# FINAL_MA.net
KiCad netlist of a schematic drawn in EAGLE
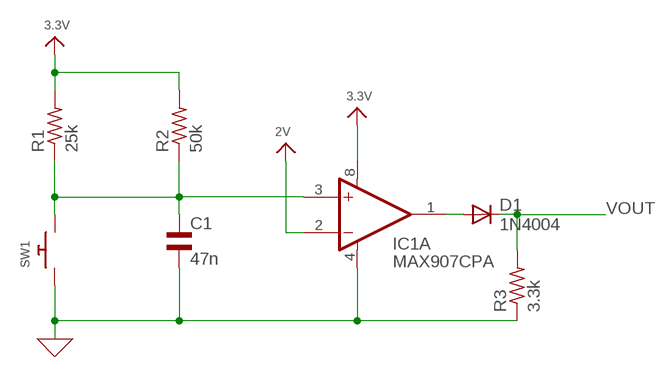
[diagram p0: schematic, sheet 1]

(export (version "E")
  (design (tool "Eeschema 10.0.6"))
  (components
    (comp (ref "C1")
      (value "47n")
      (footprint "eagle-import:EU25-10")
      (libsource (lib "eagle-import") (part "EL-BI25-10AXIAL"))
    )
    (comp (ref "D1")
      (value "1N4004")
      (footprint "eagle-import:DO41-10")
      (libsource (lib "eagle-import") (part "1N4004"))
    )
    (comp (ref "IC1")
      (value "MAX907CPA")
      (footprint "eagle-import:DIL08")
      (fields (field (name "MF") "MAXIM"))
      (libsource (lib "eagle-import") (part "MAX907CPA"))
    )
    (comp (ref "R1")
      (value "25k")
      (footprint "eagle-import:0204_5")
      (libsource (lib "eagle-import") (part "R-US_0204/5"))
    )
    (comp (ref "R2")
      (value "50k")
      (footprint "eagle-import:0204_5")
      (libsource (lib "eagle-import") (part "R-US_0204/5"))
    )
    (comp (ref "R3")
      (value "3.3k")
      (footprint "eagle-import:0204_5")
      (libsource (lib "eagle-import") (part "R-US_0204/5"))
    )
    (comp (ref "SW1")
      (value "SWITCH_PUSHBUTTONEVQ-PE")
      (footprint "eagle-import:TACT_PANA-EVQ")
      (libsource (lib "eagle-import") (part "SWITCH_PUSHBUTTONEVQ-PE"))
    )
  )
  (nets
    (net (code "1") (name "/VOUT") (class "Default")
      (node (ref "D1") (pin "C") (pinfunction "C_C") (pintype "passive"))
      (node (ref "R3") (pin "2") (pinfunction "2_2") (pintype "passive"))
    )
    (net (code "2") (name "2V") (class "Default")
      (node (ref "IC1") (pin "2") (pinfunction "-IN_2") (pintype "input"))
      (node (ref "IC1") (pin "8") (pinfunction "V+_8") (pintype "power_in"))
      (node (ref "R1") (pin "2") (pinfunction "2_2") (pintype "passive"))
      (node (ref "R2") (pin "2") (pinfunction "2_2") (pintype "passive"))
    )
    (net (code "3") (name "GND") (class "Default")
      (node (ref "C1") (pin "2") (pinfunction "2_2") (pintype "passive"))
      (node (ref "IC1") (pin "4") (pinfunction "V-_4") (pintype "power_in"))
      (node (ref "R3") (pin "1") (pinfunction "1_1") (pintype "passive"))
      (node (ref "SW1") (pin "P$1") (pinfunction "P$1_P$1") (pintype "passive"))
    )
    (net (code "4") (name "Net-(IC1A-+IN)") (class "Default")
      (node (ref "C1") (pin "1") (pinfunction "1_1") (pintype "passive"))
      (node (ref "IC1") (pin "3") (pinfunction "+IN_3") (pintype "input"))
      (node (ref "R1") (pin "1") (pinfunction "1_1") (pintype "passive"))
      (node (ref "R2") (pin "1") (pinfunction "1_1") (pintype "passive"))
      (node (ref "SW1") (pin "P$2") (pinfunction "P$2_P$2") (pintype "passive"))
    )
    (net (code "5") (name "Net-(IC1A-OUT)") (class "Default")
      (node (ref "D1") (pin "A") (pinfunction "A_A") (pintype "passive"))
      (node (ref "IC1") (pin "1") (pinfunction "OUT_1") (pintype "output"))
    )
  )
)
